# RFSwitchAnt.net
KiCad netlist of a schematic drawn in Altium Designer
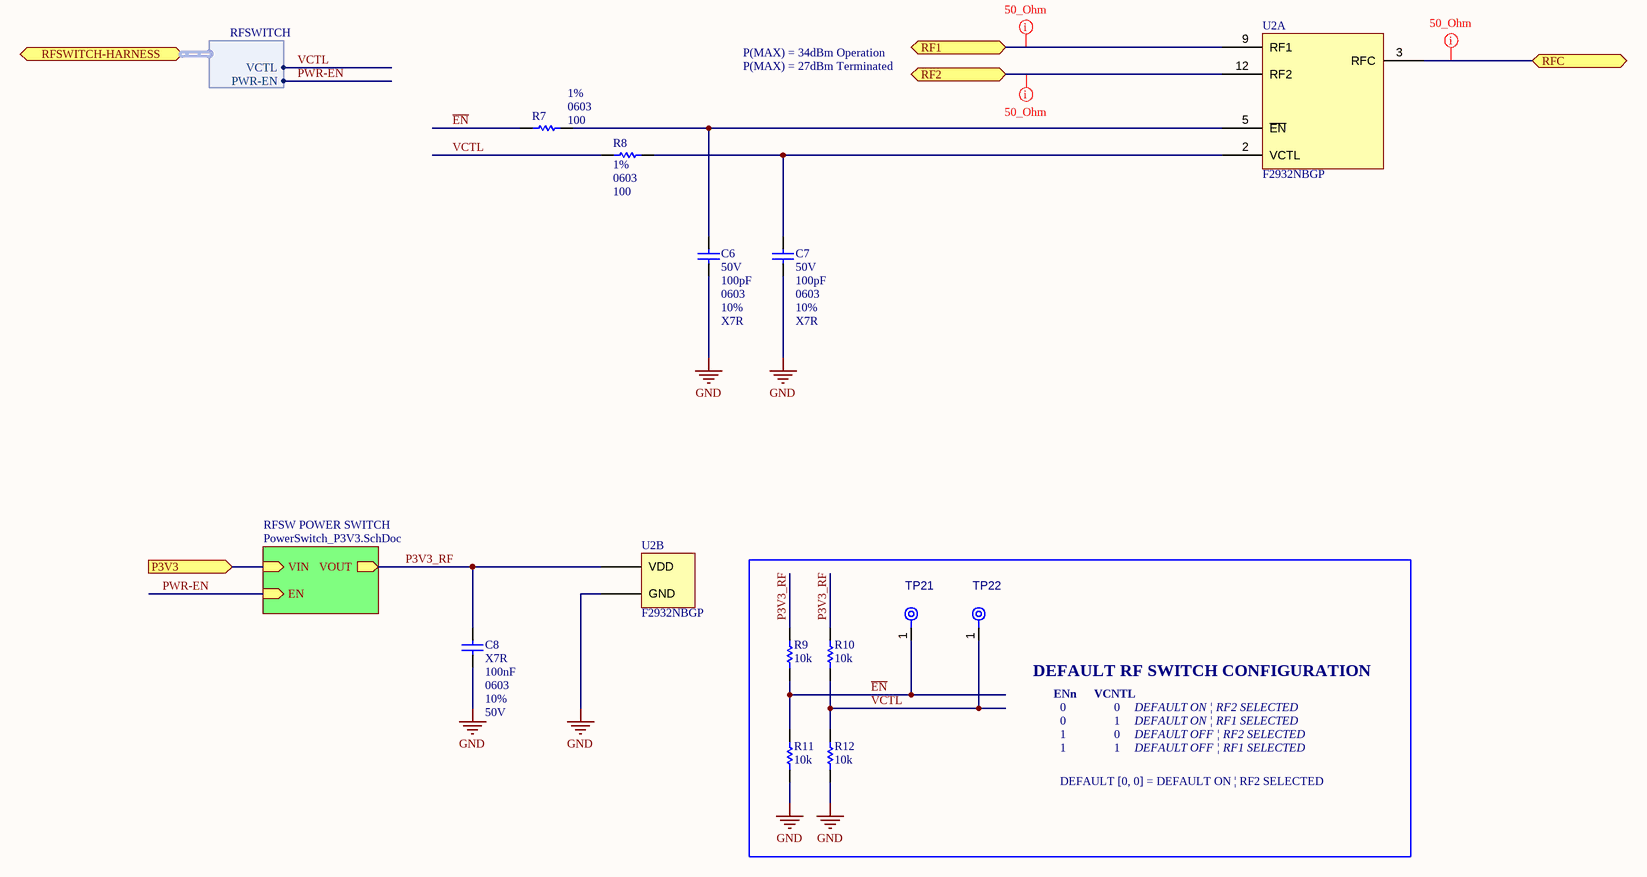
[diagram p0: RFSwitchAnt.SchDoc]

(export (version "E")
  (design (tool "Eeschema 10.0.6"))
  (components
    (comp (ref "C6")
      (value "100pF")
      (footprint "CAPC1608X90X40ML10T20")
      (description "Chip Capacitor, 100pF, +/- 10%, 50 V, X7R 0603 (1608 Metric)")
      (fields
        (field (name "VOLTAGE RATING") "50V")
        (field (name "CASE/PACKAGE") "0603")
        (field (name "TOLERANCE") "10%")
        (field (name "DIELECTRIC") "X7R")
        (field (name "Comment") "Capacitor 100pF +/- 10%, 50V, X7R, 0603")
      )
      (libsource (lib "Applied Physics Lab") (part "CAP-NP-2"))
    )
    (comp (ref "C7")
      (value "100pF")
      (footprint "CAPC1608X90X40ML10T20")
      (description "Chip Capacitor, 100pF, +/- 10%, 50 V, X7R 0603 (1608 Metric)")
      (fields
        (field (name "VOLTAGE RATING") "50V")
        (field (name "CASE/PACKAGE") "0603")
        (field (name "TOLERANCE") "10%")
        (field (name "DIELECTRIC") "X7R")
        (field (name "Comment") "Capacitor 100pF +/- 10%, 50V, X7R, 0603")
      )
      (libsource (lib "Applied Physics Lab") (part "CAP-NP-2"))
    )
    (comp (ref "C8")
      (value "100nF")
      (footprint "CAPC1608X90X40ML10T20")
      (description "Chip Capacitor, 100nF, +/- 10%, 50 V, X7R 0603 (1608 Metric)")
      (fields
        (field (name "DIELECTRIC") "X7R")
        (field (name "CASE/PACKAGE") "0603")
        (field (name "TOLERANCE") "10%")
        (field (name "VOLTAGE RATING") "50V")
        (field (name "Comment") "Capacitor 100nF +/- 10%, 50V, X7R, 0603")
      )
      (libsource (lib "Applied Physics Lab") (part "CAP-NP-2"))
    )
    (comp (ref "R7")
      (value "100")
      (footprint "RESC1609X50X30ML08T20")
      (description "Chip Resistor, 100 Ohm, +/- 1%, 0.1 W, -55 to 155 degC, 0603 (1608 Metric)")
      (fields
        (field (name "POWER") "100mW")
        (field (name "TOLERANCE") "1%")
        (field (name "CASE/PACKAGE") "0603")
        (field (name "Comment") "Resistor 100R +/-1% 0603 100 mW")
      )
      (libsource (lib "Applied Physics Lab") (part "RES-2"))
    )
    (comp (ref "R8")
      (value "100")
      (footprint "RESC1609X50X30ML08T20")
      (description "Chip Resistor, 100 Ohm, +/- 1%, 0.1 W, -55 to 155 degC, 0603 (1608 Metric)")
      (fields
        (field (name "POWER") "100mW")
        (field (name "TOLERANCE") "1%")
        (field (name "CASE/PACKAGE") "0603")
        (field (name "Comment") "Resistor 100R +/-1% 0603 100 mW")
      )
      (libsource (lib "Applied Physics Lab") (part "RES-2"))
    )
    (comp (ref "R9")
      (value "10k")
      (footprint "RESC1608X55X25ML10T15")
      (description "Chip Resistor, 10 KOhm, +/- 1%, 01 W, -55 to 155 degC, 0603 (1608 Metric)")
      (fields (field (name "TOLERANCE") "1%") (field (name "POWER") "100mW"))
      (libsource (lib "Applied Physics Lab") (part "RES-2"))
    )
    (comp (ref "R10")
      (value "10k")
      (footprint "RESC1608X55X25ML10T15")
      (description "Chip Resistor, 10 KOhm, +/- 1%, 01 W, -55 to 155 degC, 0603 (1608 Metric)")
      (fields (field (name "TOLERANCE") "1%") (field (name "POWER") "100mW"))
      (libsource (lib "Applied Physics Lab") (part "RES-2"))
    )
    (comp (ref "R11")
      (value "10k")
      (footprint "RESC1608X55X25ML10T15")
      (description "Chip Resistor, 10 KOhm, +/- 1%, 01 W, -55 to 155 degC, 0603 (1608 Metric)")
      (fields (field (name "TOLERANCE") "1%") (field (name "POWER") "100mW"))
      (libsource (lib "Applied Physics Lab") (part "RES-2"))
    )
    (comp (ref "R12")
      (value "10k")
      (footprint "RESC1608X55X25ML10T15")
      (description "Chip Resistor, 10 KOhm, +/- 1%, 01 W, -55 to 155 degC, 0603 (1608 Metric)")
      (fields (field (name "TOLERANCE") "1%") (field (name "POWER") "100mW"))
      (libsource (lib "Applied Physics Lab") (part "RES-2"))
    )
    (comp (ref "TP21")
      (value "TPAD6R-CIRCLED")
      (footprint "TP06R - Circled")
      (description "0.6mm round with a silkscreen circle.")
      (libsource (lib "Applied Physics Lab") (part "CMP-001-0001-4"))
    )
    (comp (ref "TP22")
      (value "TPAD6R-CIRCLED")
      (footprint "TP06R - Circled")
      (description "0.6mm round with a silkscreen circle.")
      (libsource (lib "Applied Physics Lab") (part "CMP-001-0001-4"))
    )
    (comp (ref "U2")
      (value "F2932NBGP")
      (footprint "QFN65P400X400X100_HS-17M")
      (description "High Reliability SP2T Absorptive RF Switch")
      (libsource (lib "Applied Physics Lab") (part "F2932NBGP-Symbol-1"))
    )
  )
  (nets
    (net (code "3") (name "/P3V3_RF") (class "Default")
      (node (ref "C8") (pin "2") (pinfunction "2_2") (pintype "passive"))
      (node (ref "R10") (pin "2") (pinfunction "2_2") (pintype "passive"))
      (node (ref "R9") (pin "2") (pinfunction "2_2") (pintype "passive"))
      (node (ref "U2") (pin "1") (pinfunction "VDD_1") (pintype "passive"))
    )
    (net (code "5") (name "/RF1") (class "Default")
      (node (ref "U2") (pin "9") (pinfunction "RF1_9") (pintype "passive"))
    )
    (net (code "6") (name "/RF2") (class "Default")
      (node (ref "U2") (pin "12") (pinfunction "RF2_12") (pintype "passive"))
    )
    (net (code "7") (name "/RFC") (class "Default")
      (node (ref "U2") (pin "3") (pinfunction "RFC_3") (pintype "passive"))
    )
    (net (code "8") (name "/VCTL") (class "Default")
      (node (ref "R10") (pin "1") (pinfunction "1_1") (pintype "passive"))
      (node (ref "R12") (pin "2") (pinfunction "2_2") (pintype "passive"))
      (node (ref "R8") (pin "2") (pinfunction "2_2") (pintype "passive"))
      (node (ref "TP22") (pin "1") (pinfunction "TP_1") (pintype "passive"))
    )
    (net (code "10") (name "/~{EN}") (class "Default")
      (node (ref "R11") (pin "2") (pinfunction "2_2") (pintype "passive"))
      (node (ref "R7") (pin "2") (pinfunction "2_2") (pintype "passive"))
      (node (ref "R9") (pin "1") (pinfunction "1_1") (pintype "passive"))
      (node (ref "TP21") (pin "1") (pinfunction "TP_1") (pintype "passive"))
    )
    (net (code "11") (name "GND") (class "Default")
      (node (ref "C6") (pin "1") (pinfunction "1_1") (pintype "passive"))
      (node (ref "C7") (pin "1") (pinfunction "1_1") (pintype "passive"))
      (node (ref "C8") (pin "1") (pinfunction "1_1") (pintype "passive"))
      (node (ref "R11") (pin "1") (pinfunction "1_1") (pintype "passive"))
      (node (ref "R12") (pin "1") (pinfunction "1_1") (pintype "passive"))
      (node (ref "U2") (pin "4") (pinfunction "GND_4") (pintype "passive"))
    )
    (net (code "12") (name "Net-(U2A-VCTL)") (class "Default")
      (node (ref "C7") (pin "2") (pinfunction "2_2") (pintype "passive"))
      (node (ref "R8") (pin "1") (pinfunction "1_1") (pintype "passive"))
      (node (ref "U2") (pin "2") (pinfunction "VCTL_2") (pintype "passive"))
    )
    (net (code "13") (name "Net-(U2A-~{EN})") (class "Default")
      (node (ref "C6") (pin "2") (pinfunction "2_2") (pintype "passive"))
      (node (ref "R7") (pin "1") (pinfunction "1_1") (pintype "passive"))
      (node (ref "U2") (pin "5") (pinfunction "~{EN}_5") (pintype "passive"))
    )
  )
)
